# Stepper_DRV8825_Interface.net
KiCad netlist of a schematic drawn in Altium Designer
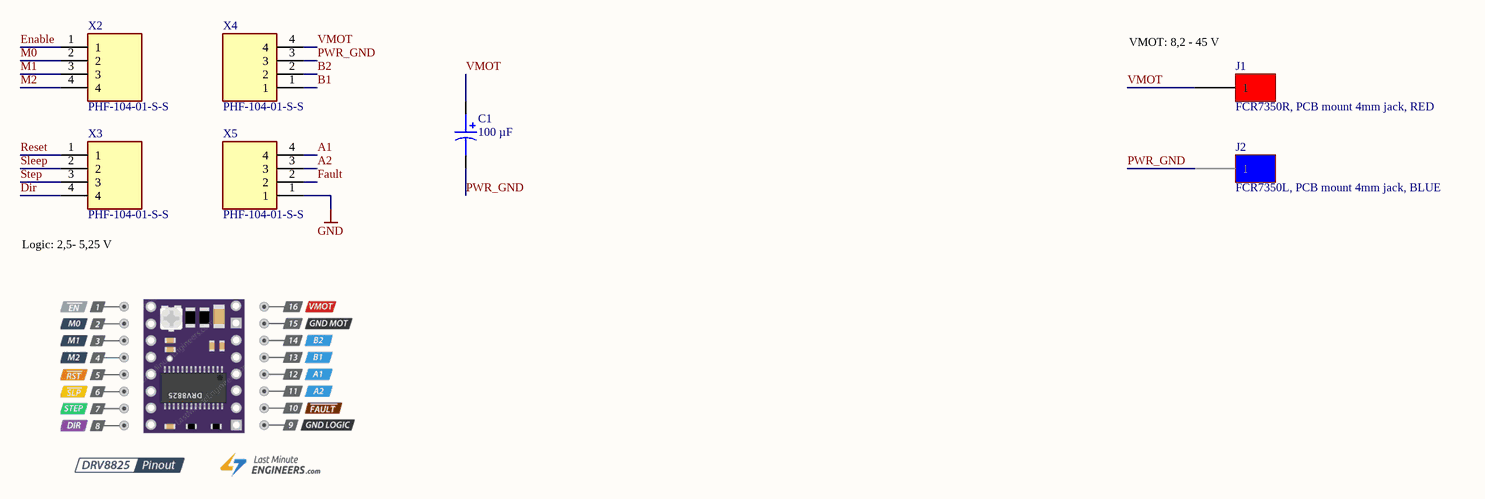
[diagram p0: Stepper_DRV8825_Interface.SchDoc]

(export (version "E")
  (design (tool "Eeschema 10.0.6"))
  (components
    (comp (ref "C1")
      (value "100 µF")
      (footprint "CAPAE830X1050N")
      (description "Capacitor EEE, 50 VDC, 100 µF")
      (fields
        (field (name "MANUFACTURER PART NUMBER") "EEE-FK1H101P")
        (field (name "MANUFACTURER") "Panasonic")
        (field (name "CREATED FROM") "MGremer")
      )
      (libsource (lib "user") (part "CAPACITOR_POLARIZED_EEE"))
    )
    (comp (ref "J1")
      (value "FCR7350R, PCB mount 4mm jack, RED")
      (footprint "FCR7350")
      (description "FCR7350B, 1000V, 24A, RED")
      (fields
        (field (name "MANUFACTURER PART NUMBER") "FCR7350R")
        (field (name "MANUFACTURER") "Cliff")
        (field (name "CREATED FROM") "DHufnagel")
      )
      (libsource (lib "user") (part "FCR7350R"))
    )
    (comp (ref "J2")
      (value "FCR7350L, PCB mount 4mm jack, BLUE")
      (footprint "FCR7350")
      (description "FCR7350B, 1000V, 24A, BLUE")
      (fields
        (field (name "MANUFACTURER PART NUMBER") "FCR7350L")
        (field (name "MANUFACTURER") "Cliff")
        (field (name "CREATED FROM") "DHufnagel")
      )
      (libsource (lib "user") (part "FCR7350L"))
    )
    (comp (ref "X2")
      (value "PHF-104-01-S-S")
      (footprint "PHF-104-01-S-S")
      (description "PIN Header")
      (fields
        (field (name "MOUSER PART NUMBER") "200-PHF10401SS")
        (field (name "MANUFACTURER") "SAMTEC")
        (field (name "CREATED FROM") "MGremer")
      )
      (libsource (lib "user") (part "PHF-104-01-S-S"))
    )
    (comp (ref "X3")
      (value "PHF-104-01-S-S")
      (footprint "PHF-104-01-S-S")
      (description "PIN Header")
      (fields
        (field (name "MOUSER PART NUMBER") "200-PHF10401SS")
        (field (name "MANUFACTURER") "SAMTEC")
        (field (name "CREATED FROM") "MGremer")
      )
      (libsource (lib "user") (part "PHF-104-01-S-S"))
    )
    (comp (ref "X4")
      (value "PHF-104-01-S-S")
      (footprint "PHF-104-01-S-S")
      (description "PIN Header")
      (fields
        (field (name "MOUSER PART NUMBER") "200-PHF10401SS")
        (field (name "MANUFACTURER") "SAMTEC")
        (field (name "CREATED FROM") "MGremer")
      )
      (libsource (lib "") (part "PHF-104-01-S-S_1"))
    )
    (comp (ref "X5")
      (value "PHF-104-01-S-S")
      (footprint "PHF-104-01-S-S")
      (description "PIN Header")
      (fields
        (field (name "MOUSER PART NUMBER") "200-PHF10401SS")
        (field (name "MANUFACTURER") "SAMTEC")
        (field (name "CREATED FROM") "MGremer")
      )
      (libsource (lib "") (part "PHF-104-01-S-S_1"))
    )
  )
  (nets
    (net (code "1") (name "/A1") (class "Default")
      (node (ref "X5") (pin "4") (pinfunction "4_4") (pintype "passive"))
    )
    (net (code "2") (name "/A2") (class "Default")
      (node (ref "X5") (pin "3") (pinfunction "3_3") (pintype "passive"))
    )
    (net (code "3") (name "/B1") (class "Default")
      (node (ref "X4") (pin "1") (pinfunction "1_1") (pintype "passive"))
    )
    (net (code "4") (name "/B2") (class "Default")
      (node (ref "X4") (pin "2") (pinfunction "2_2") (pintype "passive"))
    )
    (net (code "5") (name "/Dir") (class "Default")
      (node (ref "X3") (pin "4") (pinfunction "4_4") (pintype "passive"))
    )
    (net (code "6") (name "/Enable") (class "Default")
      (node (ref "X2") (pin "1") (pinfunction "1_1") (pintype "passive"))
    )
    (net (code "7") (name "/Fault") (class "Default")
      (node (ref "X5") (pin "2") (pinfunction "2_2") (pintype "passive"))
    )
    (net (code "8") (name "/M0") (class "Default")
      (node (ref "X2") (pin "2") (pinfunction "2_2") (pintype "passive"))
    )
    (net (code "9") (name "/M1") (class "Default")
      (node (ref "X2") (pin "3") (pinfunction "3_3") (pintype "passive"))
    )
    (net (code "10") (name "/M2") (class "Default")
      (node (ref "X2") (pin "4") (pinfunction "4_4") (pintype "passive"))
    )
    (net (code "11") (name "/PWR_GND") (class "Default")
      (node (ref "C1") (pin "2") (pinfunction "2_2") (pintype "passive"))
      (node (ref "J2") (pin "1") (pinfunction "1_1") (pintype "passive"))
      (node (ref "X4") (pin "3") (pinfunction "3_3") (pintype "passive"))
    )
    (net (code "12") (name "/Reset") (class "Default")
      (node (ref "X3") (pin "1") (pinfunction "1_1") (pintype "passive"))
    )
    (net (code "13") (name "/Sleep") (class "Default")
      (node (ref "X3") (pin "2") (pinfunction "2_2") (pintype "passive"))
    )
    (net (code "14") (name "/Step") (class "Default")
      (node (ref "X3") (pin "3") (pinfunction "3_3") (pintype "passive"))
    )
    (net (code "15") (name "/VMOT") (class "Default")
      (node (ref "C1") (pin "1") (pinfunction "1_1") (pintype "passive"))
      (node (ref "J1") (pin "1") (pinfunction "1_1") (pintype "passive"))
      (node (ref "X4") (pin "4") (pinfunction "4_4") (pintype "passive"))
    )
    (net (code "16") (name "GND") (class "Default")
      (node (ref "X5") (pin "1") (pinfunction "1_1") (pintype "passive"))
    )
  )
)
